# RF.net
KiCad netlist of a schematic drawn in Altium Designer
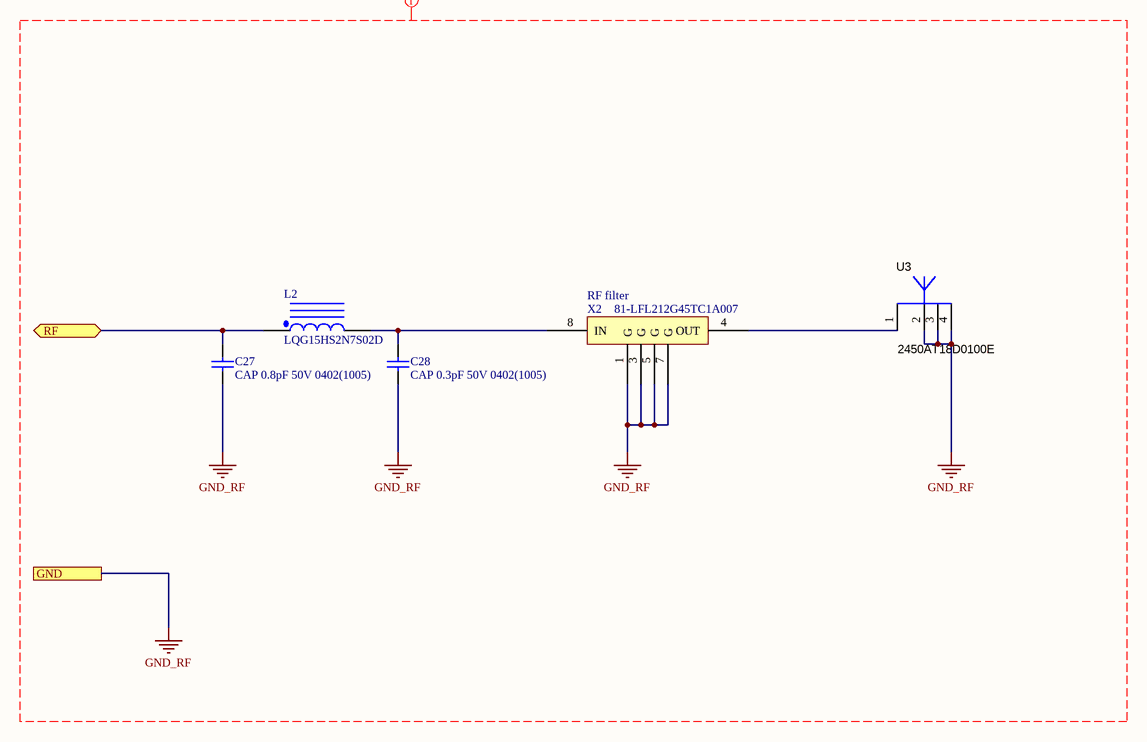
[diagram p0: RF.SchDoc]

(export (version "E")
  (design (tool "Eeschema 10.0.6"))
  (components
    (comp (ref "C27")
      (value "CAP 0.8pF 50V 0402(1005)")
      (footprint "CAPC0402(1005)60_N")
      (description "CAP 0.8pF 50V ±0.1pF 0402 (1005 Metric) Thickness 0.6mm SMD")
      (fields (field (name "TOLERANCE") "Â±0.1pF"))
      (libsource (lib "Altium Content Vault") (part "CAP"))
    )
    (comp (ref "C28")
      (value "CAP 0.3pF 50V 0402(1005)")
      (footprint "CAPC0402(1005)60_M")
      (description "CAP 0.3pF 50V ±0.05pF 0402 (1005 Metric) Thickness 0.6mm SMD")
      (fields (field (name "TOLERANCE") "Â±0.05pF"))
      (libsource (lib "Altium Content Vault") (part "CAP"))
    )
    (comp (ref "L2")
      (value "LQG15HS2N7S02D")
      (footprint "INDC1005X55X25LL05T10_A")
      (fields (field (name "MANUFACTURER") "Murata") (field (name "TOLERANCE") "±0.3nH"))
      (libsource (lib "Altium Content Vault") (part "IND-DOT-2"))
    )
    (comp (ref "U3")
      (value "2450AT18D0100E")
      (footprint "JT-2450AT18D0100E_V")
      (description "Chip RF Antenna, 2.4 to 2.5 GHz, -40 to 125 degC, 4-Pin SMD, RoHS, Tape and Reel")
      (fields (field (name "MANUFACTURER") "Johanson Technology"))
      (libsource (lib "Altium Content Vault") (part "ANTENNA_1FP_3GND"))
    )
    (comp (ref "X2")
      (value "RF filter")
      (footprint "LFL21_TC")
      (fields (field (name "SUPPLIER PART NUMBER 1") "81-LFL212G45TC1A007"))
      (libsource (lib "Coin_lib") (part "LFL212G45TC1A007"))
    )
  )
  (nets
    (net (code "1") (name "/RF") (class "Default")
      (node (ref "C27") (pin "2") (pinfunction "2_2") (pintype "passive"))
      (node (ref "L2") (pin "1") (pinfunction "1_1") (pintype "passive"))
    )
    (net (code "2") (name "GND_RF") (class "Default")
      (node (ref "C27") (pin "1") (pinfunction "1_1") (pintype "passive"))
      (node (ref "C28") (pin "1") (pinfunction "1_1") (pintype "passive"))
      (node (ref "U3") (pin "2") (pinfunction "GND_2") (pintype "power_in"))
      (node (ref "U3") (pin "3") (pinfunction "GND_3") (pintype "power_in"))
      (node (ref "U3") (pin "4") (pinfunction "GND_4") (pintype "power_in"))
      (node (ref "X2") (pin "1") (pinfunction "G_1") (pintype "passive"))
      (node (ref "X2") (pin "3") (pinfunction "G_3") (pintype "passive"))
      (node (ref "X2") (pin "5") (pinfunction "G_5") (pintype "passive"))
      (node (ref "X2") (pin "7") (pinfunction "G_7") (pintype "passive"))
    )
    (net (code "3") (name "Net-(U3-Feeding_Point)") (class "Default")
      (node (ref "U3") (pin "1") (pinfunction "Feeding_Point_1") (pintype "passive"))
      (node (ref "X2") (pin "4") (pinfunction "OUT_4") (pintype "passive"))
    )
    (net (code "4") (name "Net-(X2-IN)") (class "Default")
      (node (ref "C28") (pin "2") (pinfunction "2_2") (pintype "passive"))
      (node (ref "L2") (pin "2") (pinfunction "2_2") (pintype "passive"))
      (node (ref "X2") (pin "8") (pinfunction "IN_8") (pintype "passive"))
    )
  )
)
